# audio_breakout.net
KiCad netlist of a schematic drawn in EAGLE
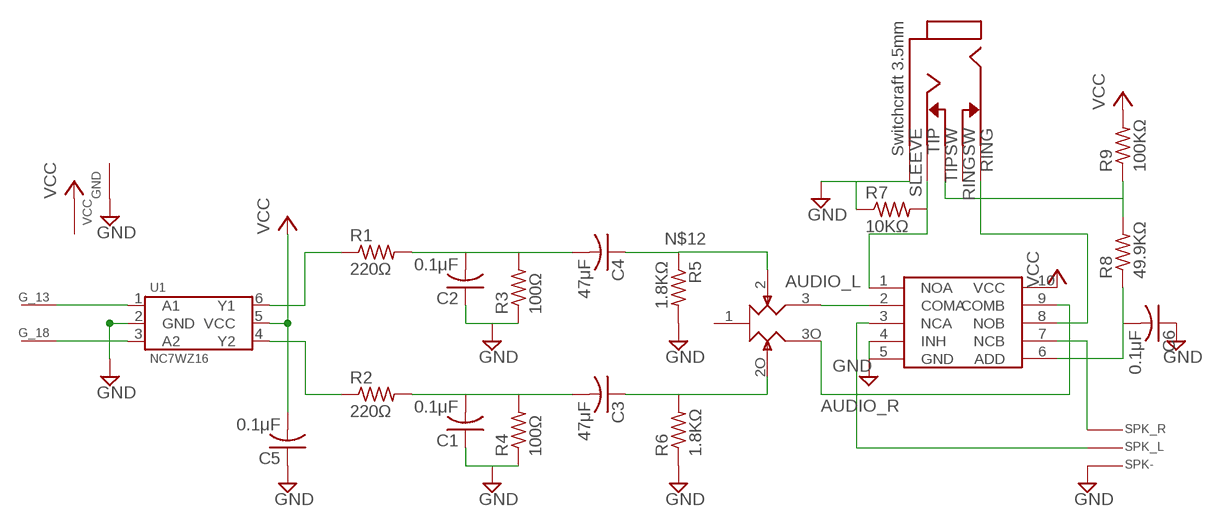
[diagram p0: schematic, sheet 1]

(export (version "E")
  (design (tool "Eeschema 10.0.6"))
  (components
    (comp (ref "C1")
      (value "0.1μF")
      (footprint "eagle-import:C0603")
      (libsource (lib "eagle-import") (part "C-USC0603"))
    )
    (comp (ref "C2")
      (value "0.1μF")
      (footprint "eagle-import:C0603")
      (libsource (lib "eagle-import") (part "C-USC0603"))
    )
    (comp (ref "C3")
      (value "47μF")
      (footprint "eagle-import:C0603")
      (libsource (lib "eagle-import") (part "C-USC0603"))
    )
    (comp (ref "C4")
      (value "47μF")
      (footprint "eagle-import:C0603")
      (libsource (lib "eagle-import") (part "C-USC0603"))
    )
    (comp (ref "C5")
      (value "0.1μF")
      (footprint "eagle-import:C0603")
      (libsource (lib "eagle-import") (part "C-USC0603"))
    )
    (comp (ref "C6")
      (value "0.1μF")
      (footprint "eagle-import:C0603")
      (libsource (lib "eagle-import") (part "C-USC0603"))
    )
    (comp (ref "GND")
      (value "THROUGH-HOLE")
      (footprint "eagle-import:THROUGH-HOLE")
      (libsource (lib "eagle-import") (part "THROUGH-HOLE"))
    )
    (comp (ref "G_13")
      (value "THROUGH-HOLE")
      (footprint "eagle-import:THROUGH-HOLE")
      (libsource (lib "eagle-import") (part "THROUGH-HOLE"))
    )
    (comp (ref "G_18")
      (value "THROUGH-HOLE")
      (footprint "eagle-import:THROUGH-HOLE")
      (libsource (lib "eagle-import") (part "THROUGH-HOLE"))
    )
    (comp (ref "R1")
      (value "220Ω")
      (footprint "eagle-import:R0603")
      (libsource (lib "eagle-import") (part "R-US_R0603"))
    )
    (comp (ref "R2")
      (value "220Ω")
      (footprint "eagle-import:R0603")
      (libsource (lib "eagle-import") (part "R-US_R0603"))
    )
    (comp (ref "R3")
      (value "100Ω")
      (footprint "eagle-import:R0603")
      (libsource (lib "eagle-import") (part "R-US_R0603"))
    )
    (comp (ref "R4")
      (value "100Ω")
      (footprint "eagle-import:R0603")
      (libsource (lib "eagle-import") (part "R-US_R0603"))
    )
    (comp (ref "R5")
      (value "1.8KΩ")
      (footprint "eagle-import:R0603")
      (libsource (lib "eagle-import") (part "R-US_R0603"))
    )
    (comp (ref "R6")
      (value "1.8KΩ")
      (footprint "eagle-import:R0603")
      (libsource (lib "eagle-import") (part "R-US_R0603"))
    )
    (comp (ref "R7")
      (value "10KΩ")
      (footprint "eagle-import:R0603")
      (libsource (lib "eagle-import") (part "R-US_R0603"))
    )
    (comp (ref "R8")
      (value "49.9KΩ")
      (footprint "eagle-import:R0603")
      (libsource (lib "eagle-import") (part "R-US_R0603"))
    )
    (comp (ref "R9")
      (value "100KΩ")
      (footprint "eagle-import:R0603")
      (libsource (lib "eagle-import") (part "R-US_R0603"))
    )
    (comp (ref "SPK-")
      (value "THROUGH-HOLE")
      (footprint "eagle-import:THROUGH-HOLE")
      (libsource (lib "eagle-import") (part "THROUGH-HOLE"))
    )
    (comp (ref "SPK_L")
      (value "THROUGH-HOLE")
      (footprint "eagle-import:THROUGH-HOLE")
      (libsource (lib "eagle-import") (part "THROUGH-HOLE"))
    )
    (comp (ref "SPK_R")
      (value "THROUGH-HOLE")
      (footprint "eagle-import:THROUGH-HOLE")
      (libsource (lib "eagle-import") (part "THROUGH-HOLE"))
    )
    (comp (ref "U$2")
      (value "SWTCHCRFT_3.5JACK5-JACK-SMD")
      (footprint "eagle-import:4-JACK-SMD")
      (libsource (lib "eagle-import") (part "SWTCHCRFT_3.5JACK5-JACK-SMD"))
    )
    (comp (ref "U$3")
      (value "10K")
      (footprint "eagle-import:RK10J12E0A0A")
      (libsource (lib "eagle-import") (part "RK10J12E0A0A"))
    )
    (comp (ref "U1")
      (value "NC7WZ16")
      (footprint "eagle-import:SC-70-6")
      (libsource (lib "eagle-import") (part "NC7WZ16"))
    )
    (comp (ref "U2")
      (value "MAX4525L")
      (footprint "eagle-import:UMAX10")
      (libsource (lib "eagle-import") (part "MAX4525L"))
    )
    (comp (ref "VCC")
      (value "THROUGH-HOLE")
      (footprint "eagle-import:THROUGH-HOLE")
      (libsource (lib "eagle-import") (part "THROUGH-HOLE"))
    )
  )
  (nets
    (net (code "1") (name "/AUDIO_L") (class "Default")
      (node (ref "U$3") (pin "3") (pinfunction "3_3") (pintype "bidirectional"))
      (node (ref "U2") (pin "2") (pinfunction "COMA_2") (pintype "bidirectional"))
    )
    (net (code "2") (name "/AUDIO_R") (class "Default")
      (node (ref "U$3") (pin "3O") (pinfunction "3O_3O") (pintype "bidirectional"))
      (node (ref "U2") (pin "9") (pinfunction "COMB_9") (pintype "bidirectional"))
    )
    (net (code "3") (name "/N$12") (class "Default")
      (node (ref "C4") (pin "1") (pinfunction "1_1") (pintype "passive"))
      (node (ref "R5") (pin "1") (pinfunction "1_1") (pintype "passive"))
      (node (ref "U$3") (pin "2") (pinfunction "2_2") (pintype "bidirectional"))
    )
    (net (code "4") (name "GND") (class "Default")
      (node (ref "C1") (pin "1") (pinfunction "1_1") (pintype "passive"))
      (node (ref "C2") (pin "1") (pinfunction "1_1") (pintype "passive"))
      (node (ref "C5") (pin "1") (pinfunction "1_1") (pintype "passive"))
      (node (ref "C6") (pin "1") (pinfunction "1_1") (pintype "passive"))
      (node (ref "GND") (pin "P$1") (pinfunction "P$1_P$1") (pintype "bidirectional"))
      (node (ref "R3") (pin "1") (pinfunction "1_1") (pintype "passive"))
      (node (ref "R4") (pin "1") (pinfunction "1_1") (pintype "passive"))
      (node (ref "R5") (pin "2") (pinfunction "2_2") (pintype "passive"))
      (node (ref "R6") (pin "1") (pinfunction "1_1") (pintype "passive"))
      (node (ref "R7") (pin "1") (pinfunction "1_1") (pintype "passive"))
      (node (ref "SPK-") (pin "P$1") (pinfunction "P$1_P$1") (pintype "bidirectional"))
      (node (ref "U$2") (pin "1") (pinfunction "1_1") (pintype "bidirectional"))
      (node (ref "U1") (pin "2") (pinfunction "GND_2") (pintype "bidirectional"))
      (node (ref "U2") (pin "4") (pinfunction "INH_4") (pintype "bidirectional"))
      (node (ref "U2") (pin "5") (pinfunction "GND_5") (pintype "bidirectional"))
    )
    (net (code "5") (name "Net-(C1-Pad2)") (class "Default")
      (node (ref "C1") (pin "2") (pinfunction "2_2") (pintype "passive"))
      (node (ref "C3") (pin "2") (pinfunction "2_2") (pintype "passive"))
      (node (ref "R2") (pin "2") (pinfunction "2_2") (pintype "passive"))
      (node (ref "R4") (pin "2") (pinfunction "2_2") (pintype "passive"))
    )
    (net (code "6") (name "Net-(C2-Pad2)") (class "Default")
      (node (ref "C2") (pin "2") (pinfunction "2_2") (pintype "passive"))
      (node (ref "C4") (pin "2") (pinfunction "2_2") (pintype "passive"))
      (node (ref "R1") (pin "2") (pinfunction "2_2") (pintype "passive"))
      (node (ref "R3") (pin "2") (pinfunction "2_2") (pintype "passive"))
    )
    (net (code "7") (name "Net-(C3-Pad1)") (class "Default")
      (node (ref "C3") (pin "1") (pinfunction "1_1") (pintype "passive"))
      (node (ref "R6") (pin "2") (pinfunction "2_2") (pintype "passive"))
      (node (ref "U$3") (pin "2O") (pinfunction "2O_2O") (pintype "bidirectional"))
    )
    (net (code "8") (name "Net-(R8-Pad2)") (class "Default")
      (node (ref "R8") (pin "2") (pinfunction "2_2") (pintype "passive"))
      (node (ref "R9") (pin "1") (pinfunction "1_1") (pintype "passive"))
      (node (ref "U$2") (pin "5") (pinfunction "5_5") (pintype "bidirectional"))
    )
    (net (code "9") (name "Net-(U1-A1)") (class "Default")
      (node (ref "G_13") (pin "P$1") (pinfunction "P$1_P$1") (pintype "bidirectional"))
      (node (ref "U1") (pin "1") (pinfunction "A1_1") (pintype "bidirectional"))
    )
    (net (code "10") (name "Net-(U1-A2)") (class "Default")
      (node (ref "G_18") (pin "P$1") (pinfunction "P$1_P$1") (pintype "bidirectional"))
      (node (ref "U1") (pin "3") (pinfunction "A2_3") (pintype "bidirectional"))
    )
    (net (code "11") (name "Net-(U1-Y1)") (class "Default")
      (node (ref "R1") (pin "1") (pinfunction "1_1") (pintype "passive"))
      (node (ref "U1") (pin "6") (pinfunction "Y1_6") (pintype "bidirectional"))
    )
    (net (code "12") (name "Net-(U1-Y2)") (class "Default")
      (node (ref "R2") (pin "1") (pinfunction "1_1") (pintype "passive"))
      (node (ref "U1") (pin "4") (pinfunction "Y2_4") (pintype "bidirectional"))
    )
    (net (code "13") (name "Net-(U2-ADD)") (class "Default")
      (node (ref "C6") (pin "2") (pinfunction "2_2") (pintype "passive"))
      (node (ref "R8") (pin "1") (pinfunction "1_1") (pintype "passive"))
      (node (ref "U2") (pin "6") (pinfunction "ADD_6") (pintype "bidirectional"))
    )
    (net (code "14") (name "Net-(U2-NCA)") (class "Default")
      (node (ref "SPK_L") (pin "P$1") (pinfunction "P$1_P$1") (pintype "bidirectional"))
      (node (ref "U2") (pin "3") (pinfunction "NCA_3") (pintype "bidirectional"))
    )
    (net (code "15") (name "Net-(U2-NCB)") (class "Default")
      (node (ref "SPK_R") (pin "P$1") (pinfunction "P$1_P$1") (pintype "bidirectional"))
      (node (ref "U2") (pin "7") (pinfunction "NCB_7") (pintype "bidirectional"))
    )
    (net (code "16") (name "Net-(U2-NOA)") (class "Default")
      (node (ref "R7") (pin "2") (pinfunction "2_2") (pintype "passive"))
      (node (ref "U$2") (pin "3") (pinfunction "3_3") (pintype "bidirectional"))
      (node (ref "U2") (pin "1") (pinfunction "NOA_1") (pintype "bidirectional"))
    )
    (net (code "17") (name "Net-(U2-NOB)") (class "Default")
      (node (ref "U$2") (pin "2") (pinfunction "2_2") (pintype "bidirectional"))
      (node (ref "U2") (pin "8") (pinfunction "NOB_8") (pintype "bidirectional"))
    )
    (net (code "18") (name "VCC") (class "Default")
      (node (ref "C5") (pin "2") (pinfunction "2_2") (pintype "passive"))
      (node (ref "R9") (pin "2") (pinfunction "2_2") (pintype "passive"))
      (node (ref "U1") (pin "5") (pinfunction "VCC_5") (pintype "bidirectional"))
      (node (ref "U2") (pin "10") (pinfunction "VCC_10") (pintype "bidirectional"))
      (node (ref "VCC") (pin "P$1") (pinfunction "P$1_P$1") (pintype "bidirectional"))
    )
    (net (code "19") (name "unconnected-(U$2-Pad4)") (class "Default")
      (node (ref "U$2") (pin "4") (pinfunction "4_4") (pintype "bidirectional"))
    )
    (net (code "20") (name "unconnected-(U$3-Pad1)") (class "Default")
      (node (ref "U$3") (pin "1") (pinfunction "1_1") (pintype "bidirectional"))
    )
  )
)
